# esquematico.net
KiCad netlist of a schematic drawn in EAGLE
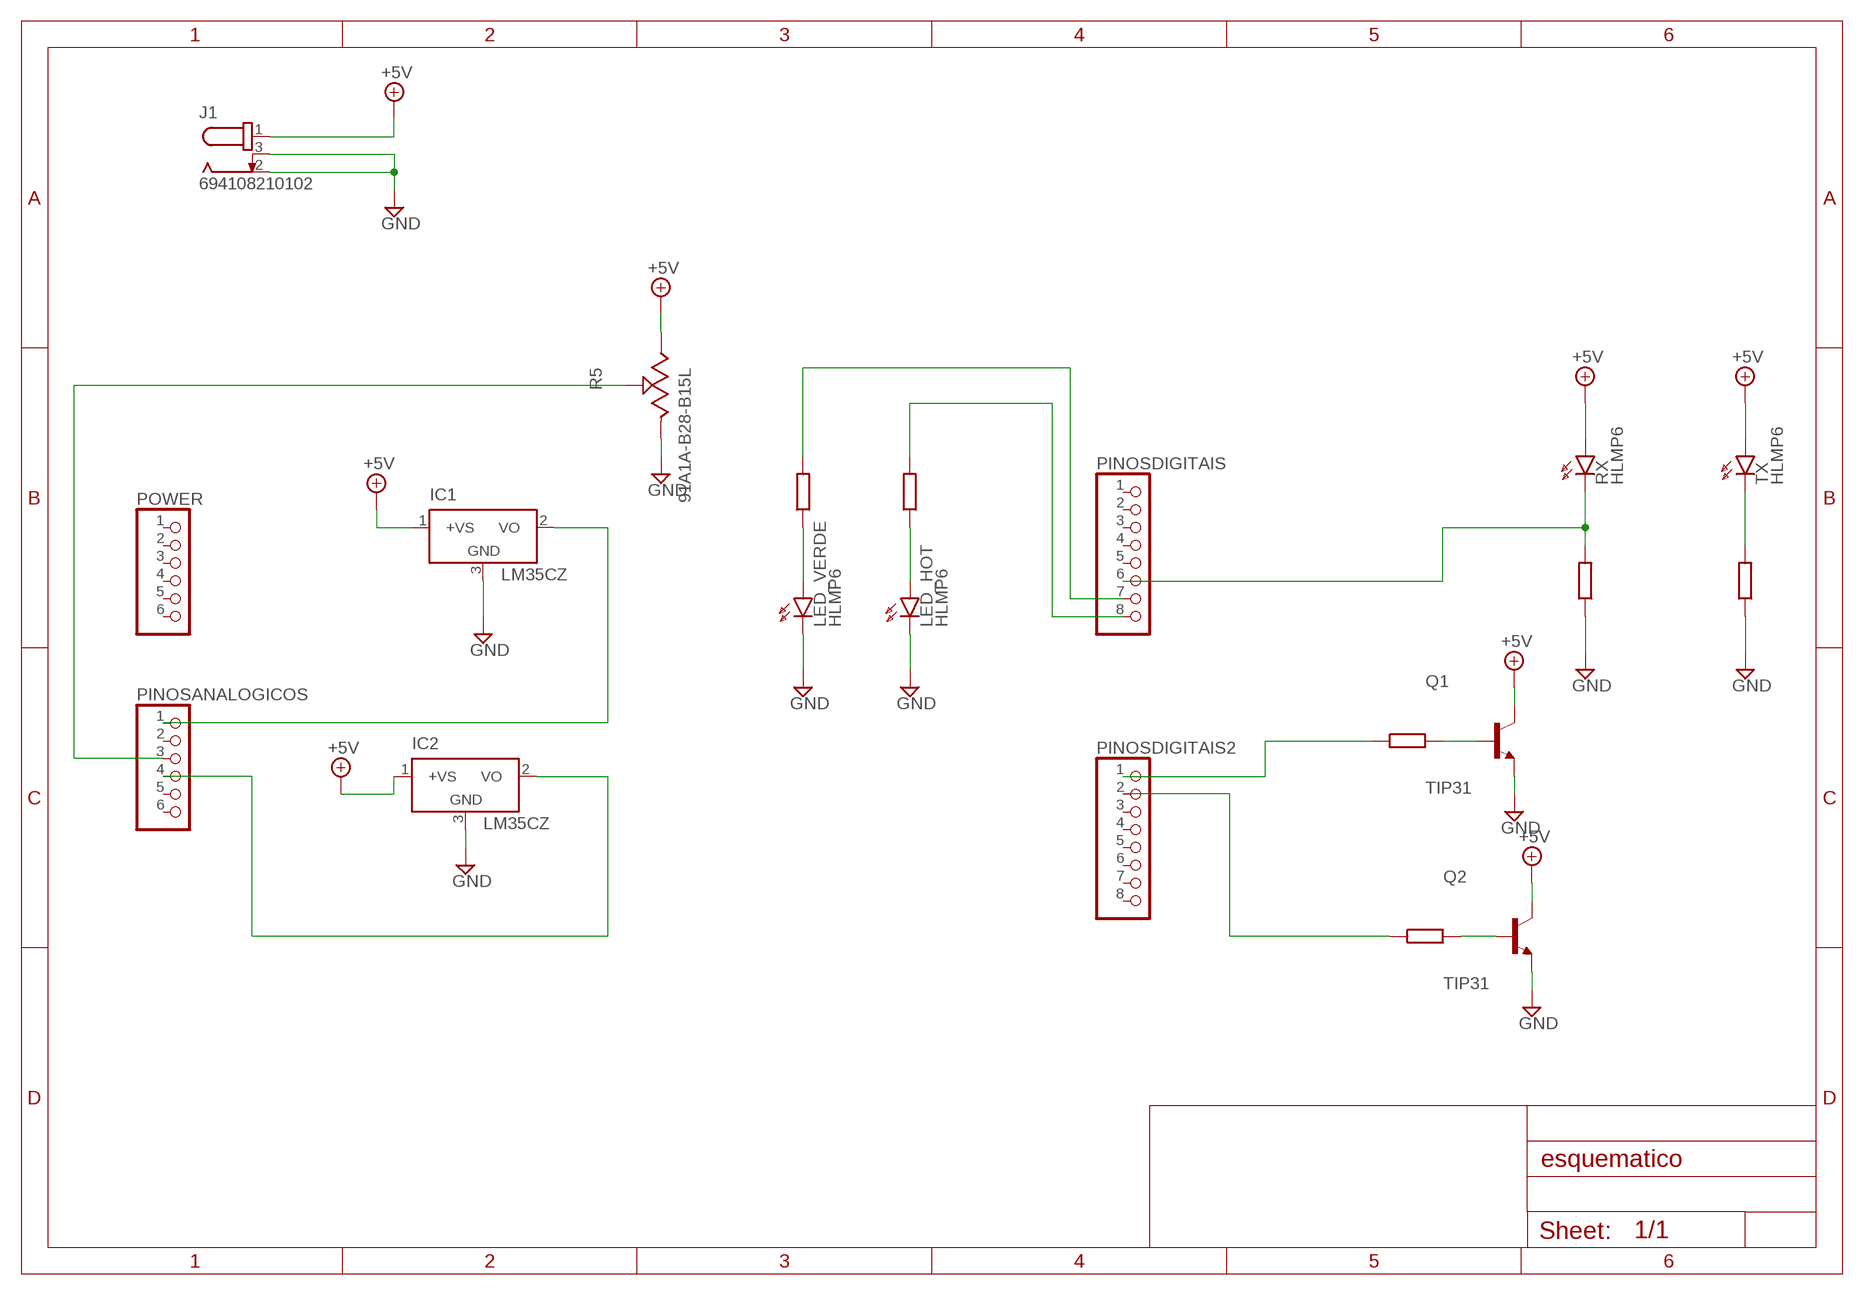
[diagram p0: schematic, sheet 1]

(export (version "E")
  (design (tool "Eeschema 10.0.6"))
  (components
    (comp (ref "IC1")
      (value "LM35CZ")
      (footprint "eagle-import:TO92")
      (libsource (lib "eagle-import") (part "LM35CZ"))
    )
    (comp (ref "IC2")
      (value "LM35CZ")
      (footprint "eagle-import:TO92")
      (libsource (lib "eagle-import") (part "LM35CZ"))
    )
    (comp (ref "J1")
      (value "694108210102")
      (footprint "eagle-import:694108210102")
      (fields (field (name "MANUFACTURER") "WURTH ELEKTRONIK") (field (name "CREATED_BY") "PCBLayout.com"))
      (libsource (lib "eagle-import") (part "694108210102"))
    )
    (comp (ref "LED_HOT")
      (value "HLMP6")
      (footprint "eagle-import:HLMP6")
      (fields (field (name "MF") "AGILENT TECHNOLOGIES") (field (name "MPN") "HLMP-6500"))
      (libsource (lib "eagle-import") (part "HLMP6"))
    )
    (comp (ref "LED_VERDE")
      (value "HLMP6")
      (footprint "eagle-import:HLMP6")
      (fields (field (name "MF") "AGILENT TECHNOLOGIES") (field (name "MPN") "HLMP-6500"))
      (libsource (lib "eagle-import") (part "HLMP6"))
    )
    (comp (ref "PINOSANALOGICOS")
      (value "PINHD-1X6")
      (footprint "eagle-import:1X06")
      (libsource (lib "eagle-import") (part "PINHD-1X6"))
    )
    (comp (ref "PINOSDIGITAIS")
      (value "PINHD-1X8")
      (footprint "eagle-import:1X08")
      (libsource (lib "eagle-import") (part "PINHD-1X8"))
    )
    (comp (ref "PINOSDIGITAIS2")
      (value "PINHD-1X8")
      (footprint "eagle-import:1X08")
      (libsource (lib "eagle-import") (part "PINHD-1X8"))
    )
    (comp (ref "POWER")
      (value "PINHD-1X6")
      (footprint "eagle-import:1X06")
      (libsource (lib "eagle-import") (part "PINHD-1X6"))
    )
    (comp (ref "Q1")
      (value "TIP31")
      (footprint "eagle-import:TO254P1060X482X2222-3")
      (fields (field (name "MF") "ON Semiconductor"))
      (libsource (lib "eagle-import") (part "TIP31"))
    )
    (comp (ref "Q2")
      (value "TIP31")
      (footprint "eagle-import:TO254P1060X482X2222-3")
      (fields (field (name "MF") "ON Semiconductor"))
      (libsource (lib "eagle-import") (part "TIP31"))
    )
    (comp (ref "R5")
      (value "91A1A-B28-B15L")
      (footprint "eagle-import:91A1A-B28-B15L-ND")
      (fields
        (field (name "DIGIKEY_PARTNO") "91A1A-B28-B15L-ND")
        (field (name "MANUFACTURER") "Bourns Inc.")
        (field (name "CREATED_BY") "PCBLayout.com")
      )
      (libsource (lib "eagle-import") (part "91A1A-B28-B15L"))
    )
    (comp (ref "RX")
      (value "HLMP6")
      (footprint "eagle-import:HLMP6")
      (fields (field (name "MF") "AGILENT TECHNOLOGIES") (field (name "MPN") "HLMP-6500"))
      (libsource (lib "eagle-import") (part "HLMP6"))
    )
    (comp (ref "TX")
      (value "HLMP6")
      (footprint "eagle-import:HLMP6")
      (fields (field (name "MF") "AGILENT TECHNOLOGIES") (field (name "MPN") "HLMP-6500"))
      (libsource (lib "eagle-import") (part "HLMP6"))
    )
  )
  (nets
    (net (code "1") (name "+5V") (class "Default")
      (node (ref "IC1") (pin "1") (pinfunction "+VS_1") (pintype "input"))
      (node (ref "IC2") (pin "1") (pinfunction "+VS_1") (pintype "input"))
      (node (ref "J1") (pin "1") (pinfunction "1_1") (pintype "passive"))
      (node (ref "Q1") (pin "2") (pinfunction "C_2") (pintype "passive"))
      (node (ref "Q2") (pin "2") (pinfunction "C_2") (pintype "passive"))
      (node (ref "R5") (pin "3") (pinfunction "3_3") (pintype "passive"))
      (node (ref "RX") (pin "A") (pinfunction "A_A") (pintype "passive"))
      (node (ref "TX") (pin "A") (pinfunction "A_A") (pintype "passive"))
    )
    (net (code "2") (name "GND") (class "Default")
      (node (ref "IC1") (pin "3") (pinfunction "GND_3") (pintype "power_in"))
      (node (ref "IC2") (pin "3") (pinfunction "GND_3") (pintype "power_in"))
      (node (ref "J1") (pin "2") (pinfunction "2_2") (pintype "passive"))
      (node (ref "J1") (pin "3") (pinfunction "3_3") (pintype "passive"))
      (node (ref "LED_HOT") (pin "K") (pinfunction "K_K") (pintype "passive"))
      (node (ref "LED_VERDE") (pin "K") (pinfunction "K_K") (pintype "passive"))
      (node (ref "Q1") (pin "3") (pinfunction "E_3") (pintype "passive"))
      (node (ref "Q2") (pin "3") (pinfunction "E_3") (pintype "passive"))
      (node (ref "R5") (pin "1") (pinfunction "1_1") (pintype "passive"))
    )
    (net (code "3") (name "Net-(IC1-VO)") (class "Default")
      (node (ref "IC1") (pin "2") (pinfunction "VO_2") (pintype "input"))
      (node (ref "PINOSANALOGICOS") (pin "1") (pinfunction "1_1") (pintype "passive"))
    )
    (net (code "4") (name "Net-(IC2-VO)") (class "Default")
      (node (ref "IC2") (pin "2") (pinfunction "VO_2") (pintype "input"))
      (node (ref "PINOSANALOGICOS") (pin "4") (pinfunction "4_4") (pintype "passive"))
    )
    (net (code "5") (name "Net-(PINOSANALOGICOS-Pad3)") (class "Default")
      (node (ref "PINOSANALOGICOS") (pin "3") (pinfunction "3_3") (pintype "passive"))
      (node (ref "R5") (pin "2") (pinfunction "2_2") (pintype "passive"))
    )
    (net (code "6") (name "Net-(PINOSDIGITAIS-Pad6)") (class "Default")
      (node (ref "PINOSDIGITAIS") (pin "6") (pinfunction "6_6") (pintype "passive"))
      (node (ref "RX") (pin "K") (pinfunction "K_K") (pintype "passive"))
    )
    (net (code "7") (name "unconnected-(LED_HOT-PadA)") (class "Default")
      (node (ref "LED_HOT") (pin "A") (pinfunction "A_A") (pintype "passive"))
    )
    (net (code "8") (name "unconnected-(LED_VERDE-PadA)") (class "Default")
      (node (ref "LED_VERDE") (pin "A") (pinfunction "A_A") (pintype "passive"))
    )
    (net (code "9") (name "unconnected-(PINOSANALOGICOS-Pad2)") (class "Default")
      (node (ref "PINOSANALOGICOS") (pin "2") (pinfunction "2_2") (pintype "passive"))
    )
    (net (code "10") (name "unconnected-(PINOSANALOGICOS-Pad5)") (class "Default")
      (node (ref "PINOSANALOGICOS") (pin "5") (pinfunction "5_5") (pintype "passive"))
    )
    (net (code "11") (name "unconnected-(PINOSANALOGICOS-Pad6)") (class "Default")
      (node (ref "PINOSANALOGICOS") (pin "6") (pinfunction "6_6") (pintype "passive"))
    )
    (net (code "12") (name "unconnected-(PINOSDIGITAIS-Pad1)") (class "Default")
      (node (ref "PINOSDIGITAIS") (pin "1") (pinfunction "1_1") (pintype "passive"))
    )
    (net (code "13") (name "unconnected-(PINOSDIGITAIS-Pad2)") (class "Default")
      (node (ref "PINOSDIGITAIS") (pin "2") (pinfunction "2_2") (pintype "passive"))
    )
    (net (code "14") (name "unconnected-(PINOSDIGITAIS-Pad3)") (class "Default")
      (node (ref "PINOSDIGITAIS") (pin "3") (pinfunction "3_3") (pintype "passive"))
    )
    (net (code "15") (name "unconnected-(PINOSDIGITAIS-Pad4)") (class "Default")
      (node (ref "PINOSDIGITAIS") (pin "4") (pinfunction "4_4") (pintype "passive"))
    )
    (net (code "16") (name "unconnected-(PINOSDIGITAIS-Pad5)") (class "Default")
      (node (ref "PINOSDIGITAIS") (pin "5") (pinfunction "5_5") (pintype "passive"))
    )
    (net (code "17") (name "unconnected-(PINOSDIGITAIS-Pad7)") (class "Default")
      (node (ref "PINOSDIGITAIS") (pin "7") (pinfunction "7_7") (pintype "passive"))
    )
    (net (code "18") (name "unconnected-(PINOSDIGITAIS-Pad8)") (class "Default")
      (node (ref "PINOSDIGITAIS") (pin "8") (pinfunction "8_8") (pintype "passive"))
    )
    (net (code "19") (name "unconnected-(PINOSDIGITAIS2-Pad1)") (class "Default")
      (node (ref "PINOSDIGITAIS2") (pin "1") (pinfunction "1_1") (pintype "passive"))
    )
    (net (code "20") (name "unconnected-(PINOSDIGITAIS2-Pad2)") (class "Default")
      (node (ref "PINOSDIGITAIS2") (pin "2") (pinfunction "2_2") (pintype "passive"))
    )
    (net (code "21") (name "unconnected-(PINOSDIGITAIS2-Pad3)") (class "Default")
      (node (ref "PINOSDIGITAIS2") (pin "3") (pinfunction "3_3") (pintype "passive"))
    )
    (net (code "22") (name "unconnected-(PINOSDIGITAIS2-Pad4)") (class "Default")
      (node (ref "PINOSDIGITAIS2") (pin "4") (pinfunction "4_4") (pintype "passive"))
    )
    (net (code "23") (name "unconnected-(PINOSDIGITAIS2-Pad5)") (class "Default")
      (node (ref "PINOSDIGITAIS2") (pin "5") (pinfunction "5_5") (pintype "passive"))
    )
    (net (code "24") (name "unconnected-(PINOSDIGITAIS2-Pad6)") (class "Default")
      (node (ref "PINOSDIGITAIS2") (pin "6") (pinfunction "6_6") (pintype "passive"))
    )
    (net (code "25") (name "unconnected-(PINOSDIGITAIS2-Pad7)") (class "Default")
      (node (ref "PINOSDIGITAIS2") (pin "7") (pinfunction "7_7") (pintype "passive"))
    )
    (net (code "26") (name "unconnected-(PINOSDIGITAIS2-Pad8)") (class "Default")
      (node (ref "PINOSDIGITAIS2") (pin "8") (pinfunction "8_8") (pintype "passive"))
    )
    (net (code "27") (name "unconnected-(POWER-Pad1)") (class "Default")
      (node (ref "POWER") (pin "1") (pinfunction "1_1") (pintype "passive"))
    )
    (net (code "28") (name "unconnected-(POWER-Pad2)") (class "Default")
      (node (ref "POWER") (pin "2") (pinfunction "2_2") (pintype "passive"))
    )
    (net (code "29") (name "unconnected-(POWER-Pad3)") (class "Default")
      (node (ref "POWER") (pin "3") (pinfunction "3_3") (pintype "passive"))
    )
    (net (code "30") (name "unconnected-(POWER-Pad4)") (class "Default")
      (node (ref "POWER") (pin "4") (pinfunction "4_4") (pintype "passive"))
    )
    (net (code "31") (name "unconnected-(POWER-Pad5)") (class "Default")
      (node (ref "POWER") (pin "5") (pinfunction "5_5") (pintype "passive"))
    )
    (net (code "32") (name "unconnected-(POWER-Pad6)") (class "Default")
      (node (ref "POWER") (pin "6") (pinfunction "6_6") (pintype "passive"))
    )
    (net (code "33") (name "unconnected-(Q1-B-Pad1)") (class "Default")
      (node (ref "Q1") (pin "1") (pinfunction "B_1") (pintype "passive"))
    )
    (net (code "34") (name "unconnected-(Q2-B-Pad1)") (class "Default")
      (node (ref "Q2") (pin "1") (pinfunction "B_1") (pintype "passive"))
    )
    (net (code "35") (name "unconnected-(TX-PadK)") (class "Default")
      (node (ref "TX") (pin "K") (pinfunction "K_K") (pintype "passive"))
    )
  )
)
